# power3V3.net
KiCad netlist of a schematic drawn in EAGLE
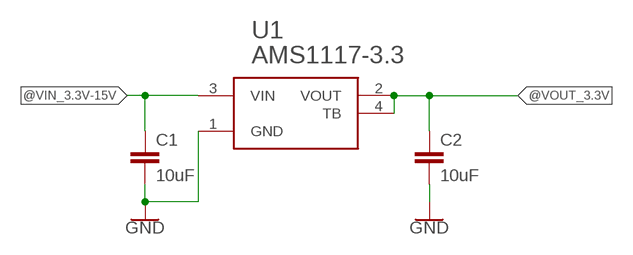
[diagram p0: schematic, sheet 1]

(export (version "E")
  (design (tool "Eeschema 10.0.6"))
  (components
    (comp (ref "C1")
      (value "10uF")
      (footprint "eagle-import:0603")
      (libsource (lib "eagle-import") (part "10UF-0603-6.3V-20%"))
    )
    (comp (ref "C2")
      (value "10uF")
      (footprint "eagle-import:0603")
      (libsource (lib "eagle-import") (part "10UF-0603-6.3V-20%"))
    )
    (comp (ref "U1")
      (value "AMS1117-3.3")
      (footprint "eagle-import:SOT290P700X180-4N")
      (libsource (lib "eagle-import") (part "AMS1117-3.3"))
    )
  )
  (nets
    (net (code "1") (name "@VIN_3.3V-15V") (class "Default")
      (node (ref "C1") (pin "1") (pinfunction "1_1") (pintype "passive"))
      (node (ref "U1") (pin "3") (pinfunction "VIN_3") (pintype "bidirectional"))
    )
    (net (code "2") (name "@VOUT_3.3V") (class "Default")
      (node (ref "C2") (pin "1") (pinfunction "1_1") (pintype "passive"))
      (node (ref "U1") (pin "2") (pinfunction "VOUT_2") (pintype "bidirectional"))
      (node (ref "U1") (pin "4") (pinfunction "TB_4") (pintype "bidirectional"))
    )
    (net (code "3") (name "GND") (class "Default")
      (node (ref "C1") (pin "2") (pinfunction "2_2") (pintype "passive"))
      (node (ref "C2") (pin "2") (pinfunction "2_2") (pintype "passive"))
      (node (ref "U1") (pin "1") (pinfunction "GND_1") (pintype "bidirectional"))
    )
  )
)
